# FMC_connector.net
KiCad netlist of a schematic drawn in Altium Designer
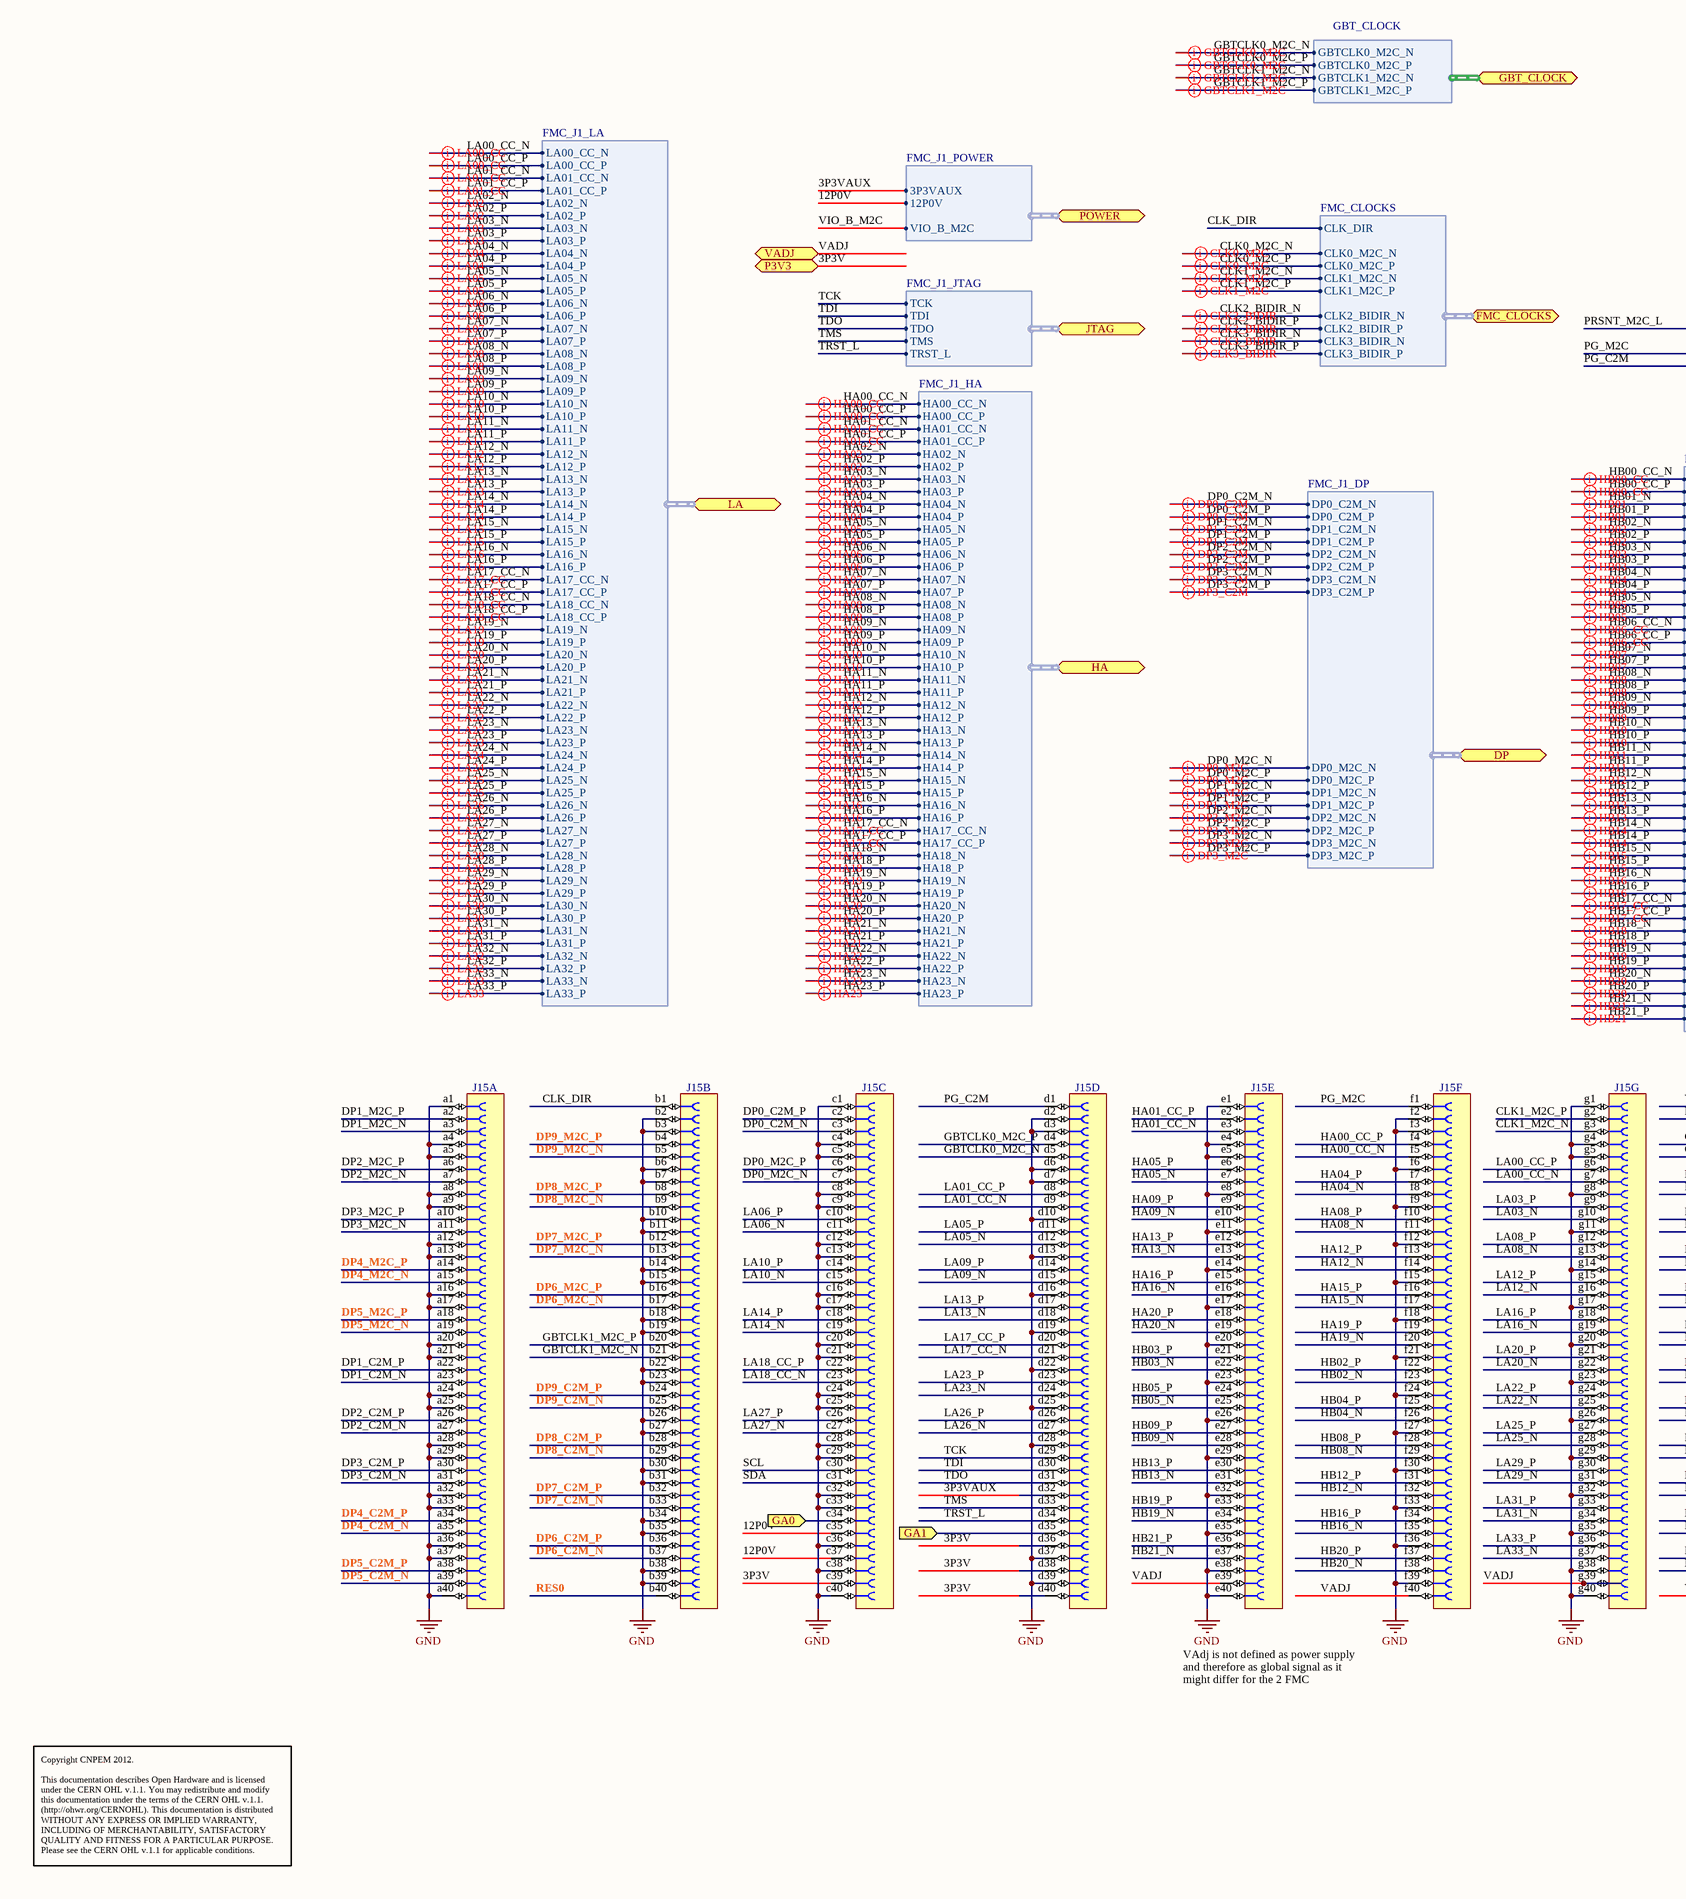
[diagram p0: FMC_connector.SchDoc, left]
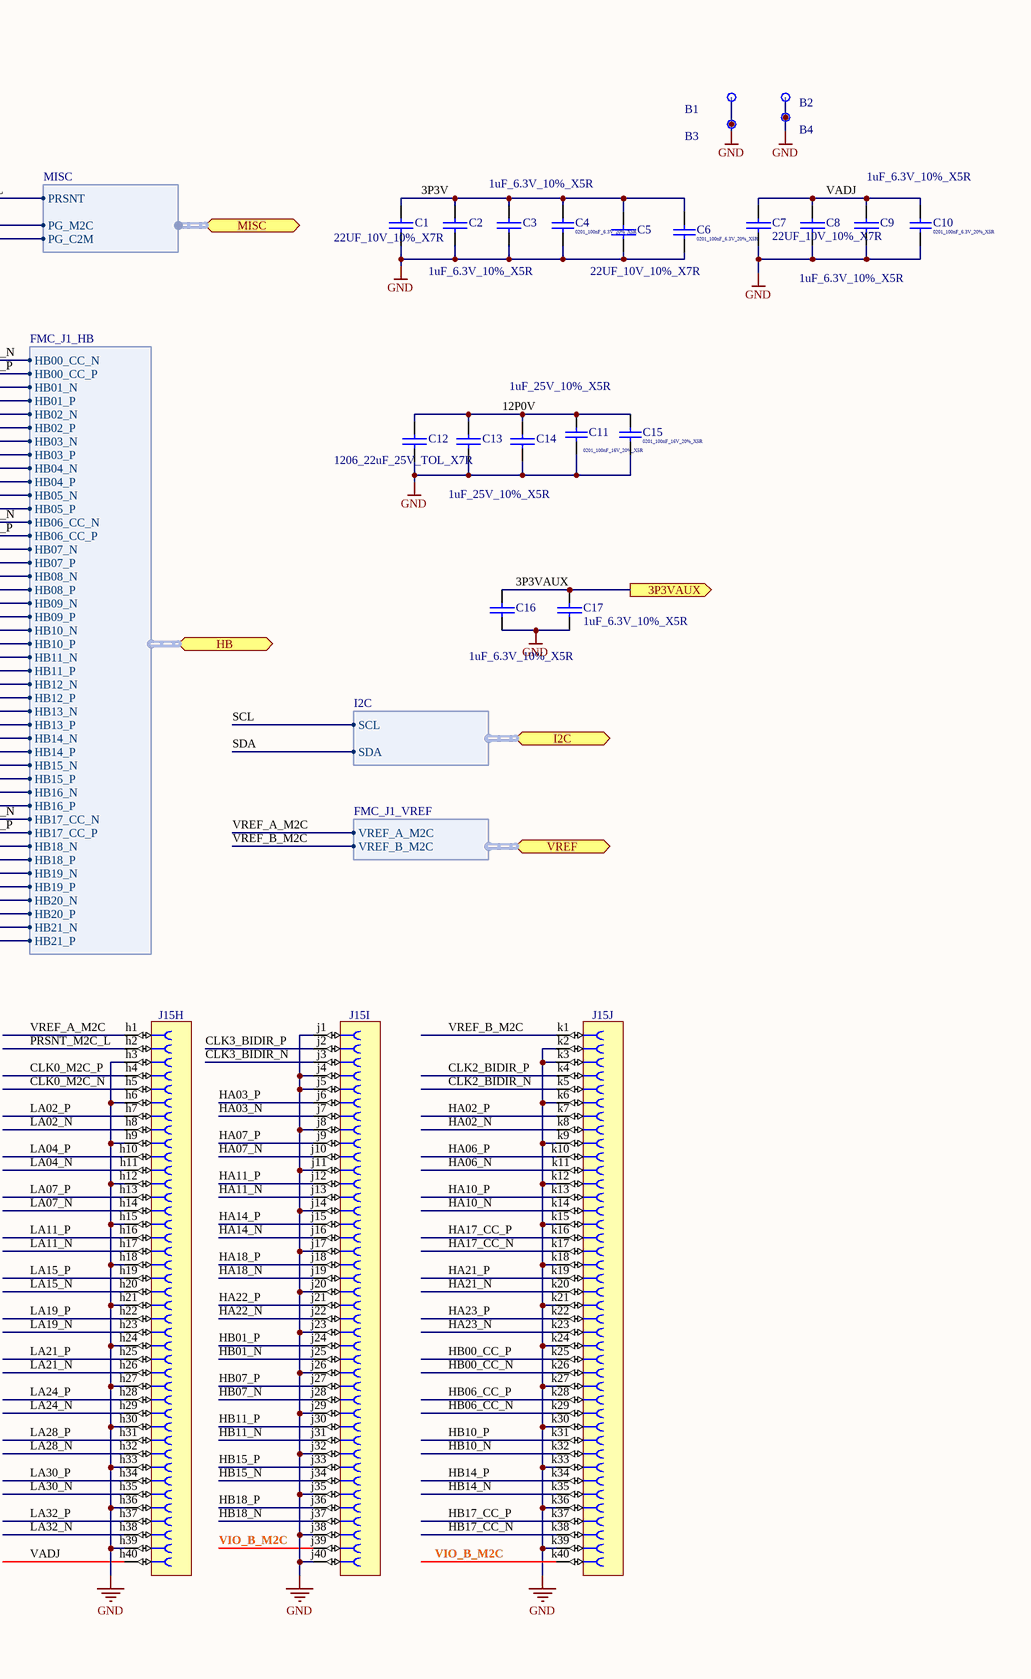
[diagram p1: FMC_connector.SchDoc, right]

(export (version "E")
  (design (tool "Eeschema 10.0.6"))
  (components
    (comp (ref "B1")
      (value "Plated Hole")
      (footprint "MTG270_500")
      (description "Single Terminal Socket")
      (fields (field (name "PART NUMBER") "PLATED_HOLE2.7_PAD5.0") (field (name "AUTHOR") "CERN DEM JMW"))
      (libsource (lib "Eletro-mechanical") (part "Single Terminal Socket"))
    )
    (comp (ref "B2")
      (value "Plated Hole")
      (footprint "MTG270_500")
      (description "Single Terminal Socket")
      (fields (field (name "PART NUMBER") "PLATED_HOLE2.7_PAD5.0") (field (name "AUTHOR") "CERN DEM JMW"))
      (libsource (lib "Eletro-mechanical") (part "Single Terminal Socket"))
    )
    (comp (ref "B3")
      (value "Plated Hole")
      (footprint "MTG270_500")
      (description "Single Terminal Socket")
      (fields (field (name "PART NUMBER") "PLATED_HOLE2.7_PAD5.0") (field (name "AUTHOR") "CERN DEM JMW"))
      (libsource (lib "Eletro-mechanical") (part "Single Terminal Socket"))
    )
    (comp (ref "B4")
      (value "Plated Hole")
      (footprint "MTG270_500")
      (description "Single Terminal Socket")
      (fields (field (name "PART NUMBER") "PLATED_HOLE2.7_PAD5.0") (field (name "AUTHOR") "CERN DEM JMW"))
      (libsource (lib "Eletro-mechanical") (part "Single Terminal Socket"))
    )
    (comp (ref "C1")
      (value "22UF_10V_10%_X7R")
      (footprint "1206C")
      (description "Capacitor SMD")
      (libsource (lib "LIBRARY_SCH") (part "CAP_SMD_1206"))
    )
    (comp (ref "C2")
      (value "1uF_6.3V_10%_X5R")
      (footprint "0603C")
      (description "Capacitor SMD")
      (libsource (lib "LIBRARY_SCH") (part "CAP_SMD_0603"))
    )
    (comp (ref "C3")
      (value "1uF_6.3V_10%_X5R")
      (footprint "0603C")
      (description "Capacitor SMD")
      (libsource (lib "LIBRARY_SCH") (part "CAP_SMD_0603"))
    )
    (comp (ref "C4")
      (value "0201_100nF_6.3V_20%_X5R")
      (footprint "CAPC0603X33N")
      (fields (field (name "PART NUMBER") "Ceramic_0201"))
      (libsource (lib "Capacitors") (part "Capacitor"))
    )
    (comp (ref "C5")
      (value "22UF_10V_10%_X7R")
      (footprint "1206C")
      (description "Capacitor SMD")
      (libsource (lib "LIBRARY_SCH") (part "CAP_SMD_1206"))
    )
    (comp (ref "C6")
      (value "0201_100nF_6.3V_20%_X5R")
      (footprint "CAPC0603X33N")
      (fields (field (name "PART NUMBER") "Ceramic_0201"))
      (libsource (lib "Capacitors") (part "Capacitor"))
    )
    (comp (ref "C7")
      (value "22UF_10V_10%_X7R")
      (footprint "1206C")
      (description "Capacitor SMD")
      (libsource (lib "LIBRARY_SCH") (part "CAP_SMD_1206"))
    )
    (comp (ref "C8")
      (value "1uF_6.3V_10%_X5R")
      (footprint "0603C")
      (description "Capacitor SMD")
      (libsource (lib "LIBRARY_SCH") (part "CAP_SMD_0603"))
    )
    (comp (ref "C9")
      (value "1uF_6.3V_10%_X5R")
      (footprint "0603C")
      (description "Capacitor SMD")
      (libsource (lib "LIBRARY_SCH") (part "CAP_SMD_0603"))
    )
    (comp (ref "C10")
      (value "0201_100nF_6.3V_20%_X5R")
      (footprint "CAPC0603X33N")
      (fields (field (name "PART NUMBER") "Ceramic_0201"))
      (libsource (lib "Capacitors") (part "Capacitor"))
    )
    (comp (ref "C11")
      (value "0201_100nF_16V_20%_X5R")
      (footprint "CAPC0603X33N")
      (fields (field (name "PART NUMBER") "Ceramic_0201"))
      (libsource (lib "Capacitors") (part "Capacitor"))
    )
    (comp (ref "C12")
      (value "1206_22uF_25V_TOL_X7R")
      (footprint "1206C")
      (description "Capacitor SMD")
      (libsource (lib "LIBRARY_SCH") (part "CAP_SMD_1206"))
    )
    (comp (ref "C13")
      (value "1uF_25V_10%_X5R")
      (footprint "0603C")
      (description "Capacitor SMD")
      (libsource (lib "LIBRARY_SCH") (part "CAP_SMD_0603"))
    )
    (comp (ref "C14")
      (value "1uF_25V_10%_X5R")
      (footprint "0603C")
      (description "Capacitor SMD")
      (libsource (lib "LIBRARY_SCH") (part "CAP_SMD_0603"))
    )
    (comp (ref "C15")
      (value "0201_100nF_16V_20%_X5R")
      (footprint "CAPC0603X33N")
      (fields (field (name "PART NUMBER") "Ceramic_0201"))
      (libsource (lib "Capacitors") (part "Capacitor"))
    )
    (comp (ref "C16")
      (value "1uF_6.3V_10%_X5R")
      (footprint "0603C")
      (description "Capacitor SMD")
      (libsource (lib "LIBRARY_SCH") (part "CAP_SMD_0603"))
    )
    (comp (ref "C17")
      (value "1uF_6.3V_10%_X5R")
      (footprint "0603C")
      (description "Capacitor SMD")
      (libsource (lib "LIBRARY_SCH") (part "CAP_SMD_0603"))
    )
    (comp (ref "J15")
      (value "VITA 57")
      (footprint "SAMTEC_ASP-134486-01")
      (description "Connector VITA 57, 400 Female contacts in 10 row abcdefghj")
      (fields
        (field (name "PART NUMBER") "SAMTEC_ASP-134486-01")
        (field (name "MANUFACTURER") "SAMTEC")
        (field (name "AUTHOR") "CERN DEM JLC")
      )
      (libsource (lib "Connectors") (part "Connector VITA 57 400 Female (abcdefghjk)"))
    )
  )
  (nets
    (net (code "12") (name "/3P3V") (class "Default")
      (node (ref "C1") (pin "1") (pinfunction "1_1") (pintype "passive"))
      (node (ref "C2") (pin "1") (pinfunction "1_1") (pintype "passive"))
      (node (ref "C3") (pin "1") (pinfunction "1_1") (pintype "passive"))
      (node (ref "C4") (pin "2") (pinfunction "2_2") (pintype "passive"))
      (node (ref "C5") (pin "1") (pinfunction "1_1") (pintype "passive"))
      (node (ref "C6") (pin "2") (pinfunction "2_2") (pintype "passive"))
      (node (ref "J15") (pin "c39") (pinfunction "c39_c39") (pintype "bidirectional"))
      (node (ref "J15") (pin "d36") (pinfunction "d36_d36") (pintype "bidirectional"))
      (node (ref "J15") (pin "d38") (pinfunction "d38_d38") (pintype "bidirectional"))
      (node (ref "J15") (pin "d40") (pinfunction "d40_d40") (pintype "bidirectional"))
    )
    (net (code "13") (name "/3P3VAUX") (class "Default")
      (node (ref "C16") (pin "1") (pinfunction "1_1") (pintype "passive"))
      (node (ref "C17") (pin "1") (pinfunction "1_1") (pintype "passive"))
      (node (ref "J15") (pin "d32") (pinfunction "d32_d32") (pintype "bidirectional"))
    )
    (net (code "14") (name "/12P0V") (class "Default")
      (node (ref "C11") (pin "2") (pinfunction "2_2") (pintype "passive"))
      (node (ref "C12") (pin "1") (pinfunction "1_1") (pintype "passive"))
      (node (ref "C13") (pin "1") (pinfunction "1_1") (pintype "passive"))
      (node (ref "C14") (pin "1") (pinfunction "1_1") (pintype "passive"))
      (node (ref "C15") (pin "2") (pinfunction "2_2") (pintype "passive"))
      (node (ref "J15") (pin "c35") (pinfunction "c35_c35") (pintype "bidirectional"))
      (node (ref "J15") (pin "c37") (pinfunction "c37_c37") (pintype "bidirectional"))
    )
    (net (code "15") (name "/CLK0_M2C_N") (class "Default")
      (node (ref "J15") (pin "h5") (pinfunction "h5_h5") (pintype "bidirectional"))
    )
    (net (code "16") (name "/CLK0_M2C_P") (class "Default")
      (node (ref "J15") (pin "h4") (pinfunction "h4_h4") (pintype "bidirectional"))
    )
    (net (code "17") (name "/CLK1_M2C_N") (class "Default")
      (node (ref "J15") (pin "g3") (pinfunction "g3_g3") (pintype "bidirectional"))
    )
    (net (code "18") (name "/CLK1_M2C_P") (class "Default")
      (node (ref "J15") (pin "g2") (pinfunction "g2_g2") (pintype "bidirectional"))
    )
    (net (code "19") (name "/CLK2_BIDIR_N") (class "Default")
      (node (ref "J15") (pin "k5") (pinfunction "k5_k5") (pintype "bidirectional"))
    )
    (net (code "20") (name "/CLK2_BIDIR_P") (class "Default")
      (node (ref "J15") (pin "k4") (pinfunction "k4_k4") (pintype "bidirectional"))
    )
    (net (code "21") (name "/CLK3_BIDIR_N") (class "Default")
      (node (ref "J15") (pin "j3") (pinfunction "j3_j3") (pintype "bidirectional"))
    )
    (net (code "22") (name "/CLK3_BIDIR_P") (class "Default")
      (node (ref "J15") (pin "j2") (pinfunction "j2_j2") (pintype "bidirectional"))
    )
    (net (code "23") (name "/CLK_DIR") (class "Default")
      (node (ref "J15") (pin "b1") (pinfunction "b1_b1") (pintype "bidirectional"))
    )
    (net (code "24") (name "/DP0_C2M_N") (class "Default")
      (node (ref "J15") (pin "c3") (pinfunction "c3_c3") (pintype "bidirectional"))
    )
    (net (code "25") (name "/DP0_C2M_P") (class "Default")
      (node (ref "J15") (pin "c2") (pinfunction "c2_c2") (pintype "bidirectional"))
    )
    (net (code "26") (name "/DP0_M2C_N") (class "Default")
      (node (ref "J15") (pin "c7") (pinfunction "c7_c7") (pintype "bidirectional"))
    )
    (net (code "27") (name "/DP0_M2C_P") (class "Default")
      (node (ref "J15") (pin "c6") (pinfunction "c6_c6") (pintype "bidirectional"))
    )
    (net (code "28") (name "/DP1_C2M_N") (class "Default")
      (node (ref "J15") (pin "a23") (pinfunction "a23_a23") (pintype "bidirectional"))
    )
    (net (code "29") (name "/DP1_C2M_P") (class "Default")
      (node (ref "J15") (pin "a22") (pinfunction "a22_a22") (pintype "bidirectional"))
    )
    (net (code "30") (name "/DP1_M2C_N") (class "Default")
      (node (ref "J15") (pin "a3") (pinfunction "a3_a3") (pintype "bidirectional"))
    )
    (net (code "31") (name "/DP1_M2C_P") (class "Default")
      (node (ref "J15") (pin "a2") (pinfunction "a2_a2") (pintype "bidirectional"))
    )
    (net (code "32") (name "/DP2_C2M_N") (class "Default")
      (node (ref "J15") (pin "a27") (pinfunction "a27_a27") (pintype "bidirectional"))
    )
    (net (code "33") (name "/DP2_C2M_P") (class "Default")
      (node (ref "J15") (pin "a26") (pinfunction "a26_a26") (pintype "bidirectional"))
    )
    (net (code "34") (name "/DP2_M2C_N") (class "Default")
      (node (ref "J15") (pin "a7") (pinfunction "a7_a7") (pintype "bidirectional"))
    )
    (net (code "35") (name "/DP2_M2C_P") (class "Default")
      (node (ref "J15") (pin "a6") (pinfunction "a6_a6") (pintype "bidirectional"))
    )
    (net (code "36") (name "/DP3_C2M_N") (class "Default")
      (node (ref "J15") (pin "a31") (pinfunction "a31_a31") (pintype "bidirectional"))
    )
    (net (code "37") (name "/DP3_C2M_P") (class "Default")
      (node (ref "J15") (pin "a30") (pinfunction "a30_a30") (pintype "bidirectional"))
    )
    (net (code "38") (name "/DP3_M2C_N") (class "Default")
      (node (ref "J15") (pin "a11") (pinfunction "a11_a11") (pintype "bidirectional"))
    )
    (net (code "39") (name "/DP3_M2C_P") (class "Default")
      (node (ref "J15") (pin "a10") (pinfunction "a10_a10") (pintype "bidirectional"))
    )
    (net (code "40") (name "/GA0") (class "Default")
      (node (ref "J15") (pin "c34") (pinfunction "c34_c34") (pintype "bidirectional"))
    )
    (net (code "41") (name "/GA1") (class "Default")
      (node (ref "J15") (pin "d35") (pinfunction "d35_d35") (pintype "bidirectional"))
    )
    (net (code "42") (name "/GBTCLK0_M2C_N") (class "Default")
      (node (ref "J15") (pin "d5") (pinfunction "d5_d5") (pintype "bidirectional"))
    )
    (net (code "43") (name "/GBTCLK0_M2C_P") (class "Default")
      (node (ref "J15") (pin "d4") (pinfunction "d4_d4") (pintype "bidirectional"))
    )
    (net (code "44") (name "/GBTCLK1_M2C_N") (class "Default")
      (node (ref "J15") (pin "b21") (pinfunction "b21_b21") (pintype "bidirectional"))
    )
    (net (code "45") (name "/GBTCLK1_M2C_P") (class "Default")
      (node (ref "J15") (pin "b20") (pinfunction "b20_b20") (pintype "bidirectional"))
    )
    (net (code "46") (name "/HA00_CC_N") (class "Default")
      (node (ref "J15") (pin "f5") (pinfunction "f5_f5") (pintype "bidirectional"))
    )
    (net (code "47") (name "/HA00_CC_P") (class "Default")
      (node (ref "J15") (pin "f4") (pinfunction "f4_f4") (pintype "bidirectional"))
    )
    (net (code "48") (name "/HA01_CC_N") (class "Default")
      (node (ref "J15") (pin "e3") (pinfunction "e3_e3") (pintype "bidirectional"))
    )
    (net (code "49") (name "/HA01_CC_P") (class "Default")
      (node (ref "J15") (pin "e2") (pinfunction "e2_e2") (pintype "bidirectional"))
    )
    (net (code "50") (name "/HA02_N") (class "Default")
      (node (ref "J15") (pin "k8") (pinfunction "k8_k8") (pintype "bidirectional"))
    )
    (net (code "51") (name "/HA02_P") (class "Default")
      (node (ref "J15") (pin "k7") (pinfunction "k7_k7") (pintype "bidirectional"))
    )
    (net (code "52") (name "/HA03_N") (class "Default")
      (node (ref "J15") (pin "j7") (pinfunction "j7_j7") (pintype "bidirectional"))
    )
    (net (code "53") (name "/HA03_P") (class "Default")
      (node (ref "J15") (pin "j6") (pinfunction "j6_j6") (pintype "bidirectional"))
    )
    (net (code "54") (name "/HA04_N") (class "Default")
      (node (ref "J15") (pin "f8") (pinfunction "f8_f8") (pintype "bidirectional"))
    )
    (net (code "55") (name "/HA04_P") (class "Default")
      (node (ref "J15") (pin "f7") (pinfunction "f7_f7") (pintype "bidirectional"))
    )
    (net (code "56") (name "/HA05_N") (class "Default")
      (node (ref "J15") (pin "e7") (pinfunction "e7_e7") (pintype "bidirectional"))
    )
    (net (code "57") (name "/HA05_P") (class "Default")
      (node (ref "J15") (pin "e6") (pinfunction "e6_e6") (pintype "bidirectional"))
    )
    (net (code "58") (name "/HA06_N") (class "Default")
      (node (ref "J15") (pin "k11") (pinfunction "k11_k11") (pintype "bidirectional"))
    )
    (net (code "59") (name "/HA06_P") (class "Default")
      (node (ref "J15") (pin "k10") (pinfunction "k10_k10") (pintype "bidirectional"))
    )
    (net (code "60") (name "/HA07_N") (class "Default")
      (node (ref "J15") (pin "j10") (pinfunction "j10_j10") (pintype "bidirectional"))
    )
    (net (code "61") (name "/HA07_P") (class "Default")
      (node (ref "J15") (pin "j9") (pinfunction "j9_j9") (pintype "bidirectional"))
    )
    (net (code "62") (name "/HA08_N") (class "Default")
      (node (ref "J15") (pin "f11") (pinfunction "f11_f11") (pintype "bidirectional"))
    )
    (net (code "63") (name "/HA08_P") (class "Default")
      (node (ref "J15") (pin "f10") (pinfunction "f10_f10") (pintype "bidirectional"))
    )
    (net (code "64") (name "/HA09_N") (class "Default")
      (node (ref "J15") (pin "e10") (pinfunction "e10_e10") (pintype "bidirectional"))
    )
    (net (code "65") (name "/HA09_P") (class "Default")
      (node (ref "J15") (pin "e9") (pinfunction "e9_e9") (pintype "bidirectional"))
    )
    (net (code "66") (name "/HA10_N") (class "Default")
      (node (ref "J15") (pin "k14") (pinfunction "k14_k14") (pintype "bidirectional"))
    )
    (net (code "67") (name "/HA10_P") (class "Default")
      (node (ref "J15") (pin "k13") (pinfunction "k13_k13") (pintype "bidirectional"))
    )
    (net (code "68") (name "/HA11_N") (class "Default")
      (node (ref "J15") (pin "j13") (pinfunction "j13_j13") (pintype "bidirectional"))
    )
    (net (code "69") (name "/HA11_P") (class "Default")
      (node (ref "J15") (pin "j12") (pinfunction "j12_j12") (pintype "bidirectional"))
    )
    (net (code "70") (name "/HA12_N") (class "Default")
      (node (ref "J15") (pin "f14") (pinfunction "f14_f14") (pintype "bidirectional"))
    )
    (net (code "71") (name "/HA12_P") (class "Default")
      (node (ref "J15") (pin "f13") (pinfunction "f13_f13") (pintype "bidirectional"))
    )
    (net (code "72") (name "/HA13_N") (class "Default")
      (node (ref "J15") (pin "e13") (pinfunction "e13_e13") (pintype "bidirectional"))
    )
    (net (code "73") (name "/HA13_P") (class "Default")
      (node (ref "J15") (pin "e12") (pinfunction "e12_e12") (pintype "bidirectional"))
    )
    (net (code "74") (name "/HA14_N") (class "Default")
      (node (ref "J15") (pin "j16") (pinfunction "j16_j16") (pintype "bidirectional"))
    )
    (net (code "75") (name "/HA14_P") (class "Default")
      (node (ref "J15") (pin "j15") (pinfunction "j15_j15") (pintype "bidirectional"))
    )
    (net (code "76") (name "/HA15_N") (class "Default")
      (node (ref "J15") (pin "f17") (pinfunction "f17_f17") (pintype "bidirectional"))
    )
    (net (code "77") (name "/HA15_P") (class "Default")
      (node (ref "J15") (pin "f16") (pinfunction "f16_f16") (pintype "bidirectional"))
    )
    (net (code "78") (name "/HA16_N") (class "Default")
      (node (ref "J15") (pin "e16") (pinfunction "e16_e16") (pintype "bidirectional"))
    )
    (net (code "79") (name "/HA16_P") (class "Default")
      (node (ref "J15") (pin "e15") (pinfunction "e15_e15") (pintype "bidirectional"))
    )
    (net (code "80") (name "/HA17_CC_N") (class "Default")
      (node (ref "J15") (pin "k17") (pinfunction "k17_k17") (pintype "bidirectional"))
    )
    (net (code "81") (name "/HA17_CC_P") (class "Default")
      (node (ref "J15") (pin "k16") (pinfunction "k16_k16") (pintype "bidirectional"))
    )
    (net (code "82") (name "/HA18_N") (class "Default")
      (node (ref "J15") (pin "j19") (pinfunction "j19_j19") (pintype "bidirectional"))
    )
    (net (code "83") (name "/HA18_P") (class "Default")
      (node (ref "J15") (pin "j18") (pinfunction "j18_j18") (pintype "bidirectional"))
    )
    (net (code "84") (name "/HA19_N") (class "Default")
      (node (ref "J15") (pin "f20") (pinfunction "f20_f20") (pintype "bidirectional"))
    )
    (net (code "85") (name "/HA19_P") (class "Default")
      (node (ref "J15") (pin "f19") (pinfunction "f19_f19") (pintype "bidirectional"))
    )
    (net (code "86") (name "/HA20_N") (class "Default")
      (node (ref "J15") (pin "e19") (pinfunction "e19_e19") (pintype "bidirectional"))
    )
    (net (code "87") (name "/HA20_P") (class "Default")
      (node (ref "J15") (pin "e18") (pinfunction "e18_e18") (pintype "bidirectional"))
    )
    (net (code "88") (name "/HA21_N") (class "Default")
      (node (ref "J15") (pin "k20") (pinfunction "k20_k20") (pintype "bidirectional"))
    )
    (net (code "89") (name "/HA21_P") (class "Default")
      (node (ref "J15") (pin "k19") (pinfunction "k19_k19") (pintype "bidirectional"))
    )
    (net (code "90") (name "/HA22_N") (class "Default")
      (node (ref "J15") (pin "j22") (pinfunction "j22_j22") (pintype "bidirectional"))
    )
    (net (code "91") (name "/HA22_P") (class "Default")
      (node (ref "J15") (pin "j21") (pinfunction "j21_j21") (pintype "bidirectional"))
    )
    (net (code "92") (name "/HA23_N") (class "Default")
      (node (ref "J15") (pin "k23") (pinfunction "k23_k23") (pintype "bidirectional"))
    )
    (net (code "93") (name "/HA23_P") (class "Default")
      (node (ref "J15") (pin "k22") (pinfunction "k22_k22") (pintype "bidirectional"))
    )
    (net (code "94") (name "/HB00_CC_N") (class "Default")
      (node (ref "J15") (pin "k26") (pinfunction "k26_k26") (pintype "bidirectional"))
    )
    (net (code "95") (name "/HB00_CC_P") (class "Default")
      (node (ref "J15") (pin "k25") (pinfunction "k25_k25") (pintype "bidirectional"))
    )
    (net (code "96") (name "/HB01_N") (class "Default")
      (node (ref "J15") (pin "j25") (pinfunction "j25_j25") (pintype "bidirectional"))
    )
    (net (code "97") (name "/HB01_P") (class "Default")
      (node (ref "J15") (pin "j24") (pinfunction "j24_j24") (pintype "bidirectional"))
    )
    (net (code "98") (name "/HB02_N") (class "Default")
      (node (ref "J15") (pin "f23") (pinfunction "f23_f23") (pintype "bidirectional"))
    )
    (net (code "99") (name "/HB02_P") (class "Default")
      (node (ref "J15") (pin "f22") (pinfunction "f22_f22") (pintype "bidirectional"))
    )
    (net (code "100") (name "/HB03_N") (class "Default")
      (node (ref "J15") (pin "e22") (pinfunction "e22_e22") (pintype "bidirectional"))
    )
    (net (code "101") (name "/HB03_P") (class "Default")
      (node (ref "J15") (pin "e21") (pinfunction "e21_e21") (pintype "bidirectional"))
    )
    (net (code "102") (name "/HB04_N") (class "Default")
      (node (ref "J15") (pin "f26") (pinfunction "f26_f26") (pintype "bidirectional"))
    )
    (net (code "103") (name "/HB04_P") (class "Default")
      (node (ref "J15") (pin "f25") (pinfunction "f25_f25") (pintype "bidirectional"))
    )
    (net (code "104") (name "/HB05_N") (class "Default")
      (node (ref "J15") (pin "e25") (pinfunction "e25_e25") (pintype "bidirectional"))
    )
    (net (code "105") (name "/HB05_P") (class "Default")
      (node (ref "J15") (pin "e24") (pinfunction "e24_e24") (pintype "bidirectional"))
    )
    (net (code "106") (name "/HB06_CC_N") (class "Default")
      (node (ref "J15") (pin "k29") (pinfunction "k29_k29") (pintype "bidirectional"))
    )
    (net (code "107") (name "/HB06_CC_P") (class "Default")
      (node (ref "J15") (pin "k28") (pinfunction "k28_k28") (pintype "bidirectional"))
    )
    (net (code "108") (name "/HB07_N") (class "Default")
      (node (ref "J15") (pin "j28") (pinfunction "j28_j28") (pintype "bidirectional"))
    )
    (net (code "109") (name "/HB07_P") (class "Default")
      (node (ref "J15") (pin "j27") (pinfunction "j27_j27") (pintype "bidirectional"))
    )
    (net (code "110") (name "/HB08_N") (class "Default")
      (node (ref "J15") (pin "f29") (pinfunction "f29_f29") (pintype "bidirectional"))
    )
    (net (code "111") (name "/HB08_P") (class "Default")
      (node (ref "J15") (pin "f28") (pinfunction "f28_f28") (pintype "bidirectional"))
    )
    (net (code "112") (name "/HB09_N") (class "Default")
      (node (ref "J15") (pin "e28") (pinfunction "e28_e28") (pintype "bidirectional"))
    )
    (net (code "113") (name "/HB09_P") (class "Default")
      (node (ref "J15") (pin "e27") (pinfunction "e27_e27") (pintype "bidirectional"))
    )
    (net (code "114") (name "/HB10_N") (class "Default")
      (node (ref "J15") (pin "k32") (pinfunction "k32_k32") (pintype "bidirectional"))
    )
    (net (code "115") (name "/HB10_P") (class "Default")
      (node (ref "J15") (pin "k31") (pinfunction "k31_k31") (pintype "bidirectional"))
    )
    (net (code "116") (name "/HB11_N") (class "Default")
      (node (ref "J15") (pin "j31") (pinfunction "j31_j31") (pintype "bidirectional"))
    )
    (net (code "117") (name "/HB11_P") (class "Default")
      (node (ref "J15") (pin "j30") (pinfunction "j30_j30") (pintype "bidirectional"))
    )
    (net (code "118") (name "/HB12_N") (class "Default")
      (node (ref "J15") (pin "f32") (pinfunction "f32_f32") (pintype "bidirectional"))
    )
    (net (code "119") (name "/HB12_P") (class "Default")
      (node (ref "J15") (pin "f31") (pinfunction "f31_f31") (pintype "bidirectional"))
    )
    (net (code "120") (name "/HB13_N") (class "Default")
      (node (ref "J15") (pin "e31") (pinfunction "e31_e31") (pintype "bidirectional"))
    )
    (net (code "121") (name "/HB13_P") (class "Default")
      (node (ref "J15") (pin "e30") (pinfunction "e30_e30") (pintype "bidirectional"))
    )
    (net (code "122") (name "/HB14_N") (class "Default")
      (node (ref "J15") (pin "k35") (pinfunction "k35_k35") (pintype "bidirectional"))
    )
    (net (code "123") (name "/HB14_P") (class "Default")
      (node (ref "J15") (pin "k34") (pinfunction "k34_k34") (pintype "bidirectional"))
    )
    (net (code "124") (name "/HB15_N") (class "Default")
      (node (ref "J15") (pin "j34") (pinfunction "j34_j34") (pintype "bidirectional"))
    )
    (net (code "125") (name "/HB15_P") (class "Default")
      (node (ref "J15") (pin "j33") (pinfunction "j33_j33") (pintype "bidirectional"))
    )
    (net (code "126") (name "/HB16_N") (class "Default")
      (node (ref "J15") (pin "f35") (pinfunction "f35_f35") (pintype "bidirectional"))
    )
    (net (code "127") (name "/HB16_P") (class "Default")
      (node (ref "J15") (pin "f34") (pinfunction "f34_f34") (pintype "bidirectional"))
    )
    (net (code "128") (name "/HB17_CC_N") (class "Default")
      (node (ref "J15") (pin "k38") (pinfunction "k38_k38") (pintype "bidirectional"))
    )
    (net (code "129") (name "/HB17_CC_P") (class "Default")
      (node (ref "J15") (pin "k37") (pinfunction "k37_k37") (pintype "bidirectional"))
    )
    (net (code "130") (name "/HB18_N") (class "Default")
      (node (ref "J15") (pin "j37") (pinfunction "j37_j37") (pintype "bidirectional"))
    )
    (net (code "131") (name "/HB18_P") (class "Default")
      (node (ref "J15") (pin "j36") (pinfunction "j36_j36") (pintype "bidirectional"))
    )
    (net (code "132") (name "/HB19_N") (class "Default")
      (node (ref "J15") (pin "e34") (pinfunction "e34_e34") (pintype "bidirectional"))
    )
    (net (code "133") (name "/HB19_P") (class "Default")
      (node (ref "J15") (pin "e33") (pinfunction "e33_e33") (pintype "bidirectional"))
    )
    (net (code "134") (name "/HB20_N") (class "Default")
      (node (ref "J15") (pin "f38") (pinfunction "f38_f38") (pintype "bidirectional"))
    )
    (net (code "135") (name "/HB20_P") (class "Default")
      (node (ref "J15") (pin "f37") (pinfunction "f37_f37") (pintype "bidirectional"))
    )
    (net (code "136") (name "/HB21_N") (class "Default")
      (node (ref "J15") (pin "e37") (pinfunction "e37_e37") (pintype "bidirectional"))
    )
    (net (code "137") (name "/HB21_P") (class "Default")
      (node (ref "J15") (pin "e36") (pinfunction "e36_e36") (pintype "bidirectional"))
    )
    (net (code "138") (name "/LA00_CC_N") (class "Default")
      (node (ref "J15") (pin "g7") (pinfunction "g7_g7") (pintype "bidirectional"))
    )
    (net (code "139") (name "/LA00_CC_P") (class "Default")
      (node (ref "J15") (pin "g6") (pinfunction "g6_g6") (pintype "bidirectional"))
    )
    (net (code "140") (name "/LA01_CC_N") (class "Default")
      (node (ref "J15") (pin "d9") (pinfunction "d9_d9") (pintype "bidirectional"))
    )
    (net (code "141") (name "/LA01_CC_P") (class "Default")
      (node (ref "J15") (pin "d8") (pinfunction "d8_d8") (pintype "bidirectional"))
    )
    (net (code "142") (name "/LA02_N") (class "Default")
      (node (ref "J15") (pin "h8") (pinfunction "h8_h8") (pintype "bidirectional"))
    )
    (net (code "143") (name "/LA02_P") (class "Default")
      (node (ref "J15") (pin "h7") (pinfunction "h7_h7") (pintype "bidirectional"))
    )
    (net (code "144") (name "/LA03_N") (class "Default")
      (node (ref "J15") (pin "g10") (pinfunction "g10_g10") (pintype "bidirectional"))
    )
    (net (code "145") (name "/LA03_P") (class "Default")
      (node (ref "J15") (pin "g9") (pinfunction "g9_g9") (pintype "bidirectional"))
    )
    (net (code "146") (name "/LA04_N") (class "Default")
      (node (ref "J15") (pin "h11") (pinfunction "h11_h11") (pintype "bidirectional"))
    )
    (net (code "147") (name "/LA04_P") (class "Default")
      (node (ref "J15") (pin "h10") (pinfunction "h10_h10") (pintype "bidirectional"))
    )
    (net (code "148") (name "/LA05_N") (class "Default")
      (node (ref "J15") (pin "d12") (pinfunction "d12_d12") (pintype "bidirectional"))
    )
    (net (code "149") (name "/LA05_P") (class "Default")
      (node (ref "J15") (pin "d11") (pinfunction "d11_d11") (pintype "bidirectional"))
    )
    (net (code "150") (name "/LA06_N") (class "Default")
      (node (ref "J15") (pin "c11") (pinfunction "c11_c11") (pintype "bidirectional"))
    )
    (net (code "151") (name "/LA06_P") (class "Default")
      (node (ref "J15") (pin "c10") (pinfunction "c10_c10") (pintype "bidirectional"))
    )
    (net (code "152") (name "/LA07_N") (class "Default")
      (node (ref "J15") (pin "h14") (pinfunction "h14_h14") (pintype "bidirectional"))
    )
    (net (code "153") (name "/LA07_P") (class "Default")
      (node (ref "J15") (pin "h13") (pinfunction "h13_h13") (pintype "bidirectional"))
    )
    (net (code "154") (name "/LA08_N") (class "Default")
      (node (ref "J15") (pin "g13") (pinfunction "g13_g13") (pintype "bidirectional"))
    )
    (net (code "155") (name "/LA08_P") (class "Default")
      (node (ref "J15") (pin "g12") (pinfunction "g12_g12") (pintype "bidirectional"))
    )
    (net (code "156") (name "/LA09_N") (class "Default")
      (node (ref "J15") (pin "d15") (pinfunction "d15_d15") (pintype "bidirectional"))
    )
    (net (code "157") (name "/LA09_P") (class "Default")
      (node (ref "J15") (pin "d14") (pinfunction "d14_d14") (pintype "bidirectional"))
    )
    (net (code "158") (name "/LA10_N") (class "Default")
      (node (ref "J15") (pin "c15") (pinfunction "c15_c15") (pintype "bidirectional"))
    )
    (net (code "159") (name "/LA10_P") (class "Default")
      (node (ref "J15") (pin "c14") (pinfunction "c14_c14") (pintype "bidirectional"))
    )
    (net (code "160") (name "/LA11_N") (class "Default")
      (node (ref "J15") (pin "h17") (pinfunction "h17_h17") (pintype "bidirectional"))
    )
    (net (code "161") (name "/LA11_P") (class "Default")
      (node (ref "J15") (pin "h16") (pinfunction "h16_h16") (pintype "bidirectional"))
    )
    (net (code "162") (name "/LA12_N") (class "Default")
      (node (ref "J15") (pin "g16") (pinfunction "g16_g16") (pintype "bidirectional"))
    )
    (net (code "163") (name "/LA12_P") (class "Default")
      (node (ref "J15") (pin "g15") (pinfunction "g15_g15") (pintype "bidirectional"))
    )
    (net (code "164") (name "/LA13_N") (class "Default")
      (node (ref "J15") (pin "d18") (pinfunction "d18_d18") (pintype "bidirectional"))
    )
    (net (code "165") (name "/LA13_P") (class "Default")
      (node (ref "J15") (pin "d17") (pinfunction "d17_d17") (pintype "bidirectional"))
    )
    (net (code "166") (name "/LA14_N") (class "Default")
      (node (ref "J15") (pin "c19") (pinfunction "c19_c19") (pintype "bidirectional"))
    )
    (net (code "167") (name "/LA14_P") (class "Default")
      (node (ref "J15") (pin "c18") (pinfunction "c18_c18") (pintype "bidirectional"))
    )
    (net (code "168") (name "/LA15_N") (class "Default")
      (node (ref "J15") (pin "h20") (pinfunction "h20_h20") (pintype "bidirectional"))
    )
    (net (code "169") (name "/LA15_P") (class "Default")
      (node (ref "J15") (pin "h19") (pinfunction "h19_h19") (pintype "bidirectional"))
    )
    (net (code "170") (name "/LA16_N") (class "Default")
      (node (ref "J15") (pin "g19") (pinfunction "g19_g19") (pintype "bidirectional"))
    )
    (net (code "171") (name "/LA16_P") (class "Default")
      (node (ref "J15") (pin "g18") (pinfunction "g18_g18") (pintype "bidirectional"))
    )
    (net (code "172") (name "/LA17_CC_N") (class "Default")
      (node (ref "J15") (pin "d21") (pinfunction "d21_d21") (pintype "bidirectional"))
    )
    (net (code "173") (name "/LA17_CC_P") (class "Default")
      (node (ref "J15") (pin "d20") (pinfunction "d20_d20") (pintype "bidirectional"))
    )
    (net (code "174") (name "/LA18_CC_N") (class "Default")
      (node (ref "J15") (pin "c23") (pinfunction "c23_c23") (pintype "bidirectional"))
    )
    (net (code "175") (name "/LA18_CC_P") (class "Default")
      (node (ref "J15") (pin "c22") (pinfunction "c22_c22") (pintype "bidirectional"))
    )
    (net (code "176") (name "/LA19_N") (class "Default")
      (node (ref "J15") (pin "h23") (pinfunction "h23_h23") (pintype "bidirectional"))
    )
    (net (code "177") (name "/LA19_P") (class "Default")
      (node (ref "J15") (pin "h22") (pinfunction "h22_h22") (pintype "bidirectional"))
    )
    (net (code "178") (name "/LA20_N") (class "Default")
      (node (ref "J15") (pin "g22") (pinfunction "g22_g22") (pintype "bidirectional"))
    )
    (net (code "179") (name "/LA20_P") (class "Default")
      (node (ref "J15") (pin "g21") (pinfunction "g21_g21") (pintype "bidirectional"))
    )
    (net (code "180") (name "/LA21_N") (class "Default")
      (node (ref "J15") (pin "h26") (pinfunction "h26_h26") (pintype "bidirectional"))
    )
    (net (code "181") (name "/LA21_P") (class "Default")
      (node (ref "J15") (pin "h25") (pinfunction "h25_h25") (pintype "bidirectional"))
    )
    (net (code "182") (name "/LA22_N") (class "Default")
      (node (ref "J15") (pin "g25") (pinfunction "g25_g25") (pintype "bidirectional"))
    )
    (net (code "183") (name "/LA22_P") (class "Default")
      (node (ref "J15") (pin "g24") (pinfunction "g24_g24") (pintype "bidirectional"))
    )
    (net (code "184") (name "/LA23_N") (class "Default")
      (node (ref "J15") (pin "d24") (pinfunction "d24_d24") (pintype "bidirectional"))
    )
    (net (code "185") (name "/LA23_P") (class "Default")
      (node (ref "J15") (pin "d23") (pinfunction "d23_d23") (pintype "bidirectional"))
    )
    (net (code "186") (name "/LA24_N") (class "Default")
      (node (ref "J15") (pin "h29") (pinfunction "h29_h29") (pintype "bidirectional"))
    )
    (net (code "187") (name "/LA24_P") (class "Default")
      (node (ref "J15") (pin "h28") (pinfunction "h28_h28") (pintype "bidirectional"))
    )
    (net (code "188") (name "/LA25_N") (class "Default")
      (node (ref "J15") (pin "g28") (pinfunction "g28_g28") (pintype "bidirectional"))
    )
    (net (code "189") (name "/LA25_P") (class "Default")
      (node (ref "J15") (pin "g27") (pinfunction "g27_g27") (pintype "bidirectional"))
    )
    (net (code "190") (name "/LA26_N") (class "Default")
      (node (ref "J15") (pin "d27") (pinfunction "d27_d27") (pintype "bidirectional"))
    )
    (net (code "191") (name "/LA26_P") (class "Default")
      (node (ref "J15") (pin "d26") (pinfunction "d26_d26") (pintype "bidirectional"))
    )
    (net (code "192") (name "/LA27_N") (class "Default")
      (node (ref "J15") (pin "c27") (pinfunction "c27_c27") (pintype "bidirectional"))
    )
    (net (code "193") (name "/LA27_P") (class "Default")
      (node (ref "J15") (pin "c26") (pinfunction "c26_c26") (pintype "bidirectional"))
    )
    (net (code "194") (name "/LA28_N") (class "Default")
      (node (ref "J15") (pin "h32") (pinfunction "h32_h32") (pintype "bidirectional"))
    )
    (net (code "195") (name "/LA28_P") (class "Default")
      (node (ref "J15") (pin "h31") (pinfunction "h31_h31") (pintype "bidirectional"))
    )
    (net (code "196") (name "/LA29_N") (class "Default")
      (node (ref "J15") (pin "g31") (pinfunction "g31_g31") (pintype "bidirectional"))
    )
    (net (code "197") (name "/LA29_P") (class "Default")
      (node (ref "J15") (pin "g30") (pinfunction "g30_g30") (pintype "bidirectional"))
    )
    (net (code "198") (name "/LA30_N") (class "Default")
      (node (ref "J15") (pin "h35") (pinfunction "h35_h35") (pintype "bidirectional"))
    )
    (net (code "199") (name "/LA30_P") (class "Default")
      (node (ref "J15") (pin "h34") (pinfunction "h34_h34") (pintype "bidirectional"))
    )
    (net (code "200") (name "/LA31_N") (class "Default")
      (node (ref "J15") (pin "g34") (pinfunction "g34_g34") (pintype "bidirectional"))
    )
    (net (code "201") (name "/LA31_P") (class "Default")
      (node (ref "J15") (pin "g33") (pinfunction "g33_g33") (pintype "bidirectional"))
    )
    (net (code "202") (name "/LA32_N") (class "Default")
      (node (ref "J15") (pin "h38") (pinfunction "h38_h38") (pintype "bidirectional"))
    )
    (net (code "203") (name "/LA32_P") (class "Default")
      (node (ref "J15") (pin "h37") (pinfunction "h37_h37") (pintype "bidirectional"))
    )
    (net (code "204") (name "/LA33_N") (class "Default")
      (node (ref "J15") (pin "g37") (pinfunction "g37_g37") (pintype "bidirectional"))
    )
    (net (code "205") (name "/LA33_P") (class "Default")
      (node (ref "J15") (pin "g36") (pinfunction "g36_g36") (pintype "bidirectional"))
    )
    (net (code "206") (name "/PG_C2M") (class "Default")
      (node (ref "J15") (pin "d1") (pinfunction "d1_d1") (pintype "bidirectional"))
    )
    (net (code "207") (name "/PG_M2C") (class "Default")
      (node (ref "J15") (pin "f1") (pinfunction "f1_f1") (pintype "bidirectional"))
    )
    (net (code "208") (name "/PRSNT_M2C_L") (class "Default")
      (node (ref "J15") (pin "h2") (pinfunction "h2_h2") (pintype "bidirectional"))
    )
    (net (code "209") (name "/SCL") (class "Default")
      (node (ref "J15") (pin "c30") (pinfunction "c30_c30") (pintype "bidirectional"))
    )
    (net (code "210") (name "/SDA") (class "Default")
      (node (ref "J15") (pin "c31") (pinfunction "c31_c31") (pintype "bidirectional"))
    )
    (net (code "211") (name "/TCK") (class "Default")
      (node (ref "J15") (pin "d29") (pinfunction "d29_d29") (pintype "bidirectional"))
    )
    (net (code "212") (name "/TDI") (class "Default")
      (node (ref "J15") (pin "d30") (pinfunction "d30_d30") (pintype "bidirectional"))
    )
    (net (code "213") (name "/TDO") (class "Default")
      (node (ref "J15") (pin "d31") (pinfunction "d31_d31") (pintype "bidirectional"))
    )
    (net (code "214") (name "/TMS") (class "Default")
      (node (ref "J15") (pin "d33") (pinfunction "d33_d33") (pintype "bidirectional"))
    )
    (net (code "215") (name "/TRST_L") (class "Default")
      (node (ref "J15") (pin "d34") (pinfunction "d34_d34") (pintype "bidirectional"))
    )
    (net (code "216") (name "/VADJ") (class "Default")
      (node (ref "C10") (pin "2") (pinfunction "2_2") (pintype "passive"))
      (node (ref "C7") (pin "1") (pinfunction "1_1") (pintype "passive"))
      (node (ref "C8") (pin "1") (pinfunction "1_1") (pintype "passive"))
      (node (ref "C9") (pin "1") (pinfunction "1_1") (pintype "passive"))
      (node (ref "J15") (pin "e39") (pinfunction "e39_e39") (pintype "bidirectional"))
      (node (ref "J15") (pin "f40") (pinfunction "f40_f40") (pintype "bidirectional"))
      (node (ref "J15") (pin "g39") (pinfunction "g39_g39") (pintype "bidirectional"))
      (node (ref "J15") (pin "h40") (pinfunction "h40_h40") (pintype "bidirectional"))
    )
    (net (code "218") (name "/VREF_A_M2C") (class "Default")
      (node (ref "J15") (pin "h1") (pinfunction "h1_h1") (pintype "bidirectional"))
    )
    (net (code "219") (name "/VREF_B_M2C") (class "Default")
      (node (ref "J15") (pin "k1") (pinfunction "k1_k1") (pintype "bidirectional"))
    )
    (net (code "231") (name "GND") (class "Default")
      (node (ref "B1") (pin "1") (pinfunction "1_1") (pintype "bidirectional"))
      (node (ref "B2") (pin "1") (pinfunction "1_1") (pintype "bidirectional"))
      (node (ref "B3") (pin "1") (pinfunction "1_1") (pintype "bidirectional"))
      (node (ref "B4") (pin "1") (pinfunction "1_1") (pintype "bidirectional"))
      (node (ref "C1") (pin "2") (pinfunction "2_2") (pintype "passive"))
      (node (ref "C10") (pin "1") (pinfunction "1_1") (pintype "passive"))
      (node (ref "C11") (pin "1") (pinfunction "1_1") (pintype "passive"))
      (node (ref "C12") (pin "2") (pinfunction "2_2") (pintype "passive"))
      (node (ref "C13") (pin "2") (pinfunction "2_2") (pintype "passive"))
      (node (ref "C14") (pin "2") (pinfunction "2_2") (pintype "passive"))
      (node (ref "C15") (pin "1") (pinfunction "1_1") (pintype "passive"))
      (node (ref "C16") (pin "2") (pinfunction "2_2") (pintype "passive"))
      (node (ref "C17") (pin "2") (pinfunction "2_2") (pintype "passive"))
      (node (ref "C2") (pin "2") (pinfunction "2_2") (pintype "passive"))
      (node (ref "C3") (pin "2") (pinfunction "2_2") (pintype "passive"))
      (node (ref "C4") (pin "1") (pinfunction "1_1") (pintype "passive"))
      (node (ref "C5") (pin "2") (pinfunction "2_2") (pintype "passive"))
      (node (ref "C6") (pin "1") (pinfunction "1_1") (pintype "passive"))
      (node (ref "C7") (pin "2") (pinfunction "2_2") (pintype "passive"))
      (node (ref "C8") (pin "2") (pinfunction "2_2") (pintype "passive"))
      (node (ref "C9") (pin "2") (pinfunction "2_2") (pintype "passive"))
      (node (ref "J15") (pin "a1") (pinfunction "a1_a1") (pintype "bidirectional"))
      (node (ref "J15") (pin "a12") (pinfunction "a12_a12") (pintype "bidirectional"))
      (node (ref "J15") (pin "a13") (pinfunction "a13_a13") (pintype "bidirectional"))
      (node (ref "J15") (pin "a16") (pinfunction "a16_a16") (pintype "bidirectional"))
      (node (ref "J15") (pin "a17") (pinfunction "a17_a17") (pintype "bidirectional"))
      (node (ref "J15") (pin "a20") (pinfunction "a20_a20") (pintype "bidirectional"))
      (node (ref "J15") (pin "a21") (pinfunction "a21_a21") (pintype "bidirectional"))
      (node (ref "J15") (pin "a24") (pinfunction "a24_a24") (pintype "bidirectional"))
      (node (ref "J15") (pin "a25") (pinfunction "a25_a25") (pintype "bidirectional"))
      (node (ref "J15") (pin "a28") (pinfunction "a28_a28") (pintype "bidirectional"))
      (node (ref "J15") (pin "a29") (pinfunction "a29_a29") (pintype "bidirectional"))
      (node (ref "J15") (pin "a32") (pinfunction "a32_a32") (pintype "bidirectional"))
      (node (ref "J15") (pin "a33") (pinfunction "a33_a33") (pintype "bidirectional"))
      (node (ref "J15") (pin "a36") (pinfunction "a36_a36") (pintype "bidirectional"))
      (node (ref "J15") (pin "a37") (pinfunction "a37_a37") (pintype "bidirectional"))
      (node (ref "J15") (pin "a4") (pinfunction "a4_a4") (pintype "bidirectional"))
      (node (ref "J15") (pin "a40") (pinfunction "a40_a40") (pintype "bidirectional"))
      (node (ref "J15") (pin "a5") (pinfunction "a5_a5") (pintype "bidirectional"))
      (node (ref "J15") (pin "a8") (pinfunction "a8_a8") (pintype "bidirectional"))
      (node (ref "J15") (pin "a9") (pinfunction "a9_a9") (pintype "bidirectional"))
      (node (ref "J15") (pin "b10") (pinfunction "b10_b10") (pintype "bidirectional"))
      (node (ref "J15") (pin "b11") (pinfunction "b11_b11") (pintype "bidirectional"))
      (node (ref "J15") (pin "b14") (pinfunction "b14_b14") (pintype "bidirectional"))
      (node (ref "J15") (pin "b15") (pinfunction "b15_b15") (pintype "bidirectional"))
      (node (ref "J15") (pin "b18") (pinfunction "b18_b18") (pintype "bidirectional"))
      (node (ref "J15") (pin "b19") (pinfunction "b19_b19") (pintype "bidirectional"))
      (node (ref "J15") (pin "b2") (pinfunction "b2_b2") (pintype "bidirectional"))
      (node (ref "J15") (pin "b22") (pinfunction "b22_b22") (pintype "bidirectional"))
      (node (ref "J15") (pin "b23") (pinfunction "b23_b23") (pintype "bidirectional"))
      (node (ref "J15") (pin "b26") (pinfunction "b26_b26") (pintype "bidirectional"))
      (node (ref "J15") (pin "b27") (pinfunction "b27_b27") (pintype "bidirectional"))
      (node (ref "J15") (pin "b3") (pinfunction "b3_b3") (pintype "bidirectional"))
      (node (ref "J15") (pin "b30") (pinfunction "b30_b30") (pintype "bidirectional"))
      (node (ref "J15") (pin "b31") (pinfunction "b31_b31") (pintype "bidirectional"))
      (node (ref "J15") (pin "b34") (pinfunction "b34_b34") (pintype "bidirectional"))
      (node (ref "J15") (pin "b35") (pinfunction "b35_b35") (pintype "bidirectional"))
      (node (ref "J15") (pin "b38") (pinfunction "b38_b38") (pintype "bidirectional"))
      (node (ref "J15") (pin "b39") (pinfunction "b39_b39") (pintype "bidirectional"))
      (node (ref "J15") (pin "b6") (pinfunction "b6_b6") (pintype "bidirectional"))
      (node (ref "J15") (pin "b7") (pinfunction "b7_b7") (pintype "bidirectional"))
      (node (ref "J15") (pin "c1") (pinfunction "c1_c1") (pintype "bidirectional"))
      (node (ref "J15") (pin "c12") (pinfunction "c12_c12") (pintype "bidirectional"))
      (node (ref "J15") (pin "c13") (pinfunction "c13_c13") (pintype "bidirectional"))
      (node (ref "J15") (pin "c16") (pinfunction "c16_c16") (pintype "bidirectional"))
      (node (ref "J15") (pin "c17") (pinfunction "c17_c17") (pintype "bidirectional"))
      (node (ref "J15") (pin "c20") (pinfunction "c20_c20") (pintype "bidirectional"))
      (node (ref "J15") (pin "c21") (pinfunction "c21_c21") (pintype "bidirectional"))
      (node (ref "J15") (pin "c24") (pinfunction "c24_c24") (pintype "bidirectional"))
      (node (ref "J15") (pin "c25") (pinfunction "c25_c25") (pintype "bidirectional"))
      (node (ref "J15") (pin "c28") (pinfunction "c28_c28") (pintype "bidirectional"))
      (node (ref "J15") (pin "c29") (pinfunction "c29_c29") (pintype "bidirectional"))
      (node (ref "J15") (pin "c32") (pinfunction "c32_c32") (pintype "bidirectional"))
      (node (ref "J15") (pin "c33") (pinfunction "c33_c33") (pintype "bidirectional"))
      (node (ref "J15") (pin "c36") (pinfunction "c36_c36") (pintype "bidirectional"))
      (node (ref "J15") (pin "c38") (pinfunction "c38_c38") (pintype "bidirectional"))
      (node (ref "J15") (pin "c4") (pinfunction "c4_c4") (pintype "bidirectional"))
      (node (ref "J15") (pin "c40") (pinfunction "c40_c40") (pintype "bidirectional"))
      (node (ref "J15") (pin "c5") (pinfunction "c5_c5") (pintype "bidirectional"))
      (node (ref "J15") (pin "c8") (pinfunction "c8_c8") (pintype "bidirectional"))
      (node (ref "J15") (pin "c9") (pinfunction "c9_c9") (pintype "bidirectional"))
      (node (ref "J15") (pin "d10") (pinfunction "d10_d10") (pintype "bidirectional"))
      (node (ref "J15") (pin "d13") (pinfunction "d13_d13") (pintype "bidirectional"))
      (node (ref "J15") (pin "d16") (pinfunction "d16_d16") (pintype "bidirectional"))
      (node (ref "J15") (pin "d19") (pinfunction "d19_d19") (pintype "bidirectional"))
      (node (ref "J15") (pin "d2") (pinfunction "d2_d2") (pintype "bidirectional"))
      (node (ref "J15") (pin "d22") (pinfunction "d22_d22") (pintype "bidirectional"))
      (node (ref "J15") (pin "d25") (pinfunction "d25_d25") (pintype "bidirectional"))
      (node (ref "J15") (pin "d28") (pinfunction "d28_d28") (pintype "bidirectional"))
      (node (ref "J15") (pin "d3") (pinfunction "d3_d3") (pintype "bidirectional"))
      (node (ref "J15") (pin "d37") (pinfunction "d37_d37") (pintype "bidirectional"))
      (node (ref "J15") (pin "d39") (pinfunction "d39_d39") (pintype "bidirectional"))
      (node (ref "J15") (pin "d6") (pinfunction "d6_d6") (pintype "bidirectional"))
      (node (ref "J15") (pin "d7") (pinfunction "d7_d7") (pintype "bidirectional"))
      (node (ref "J15") (pin "e1") (pinfunction "e1_e1") (pintype "bidirectional"))
      (node (ref "J15") (pin "e11") (pinfunction "e11_e11") (pintype "bidirectional"))
      (node (ref "J15") (pin "e14") (pinfunction "e14_e14") (pintype "bidirectional"))
      (node (ref "J15") (pin "e17") (pinfunction "e17_e17") (pintype "bidirectional"))
      (node (ref "J15") (pin "e20") (pinfunction "e20_e20") (pintype "bidirectional"))
      (node (ref "J15") (pin "e23") (pinfunction "e23_e23") (pintype "bidirectional"))
      (node (ref "J15") (pin "e26") (pinfunction "e26_e26") (pintype "bidirectional"))
      (node (ref "J15") (pin "e29") (pinfunction "e29_e29") (pintype "bidirectional"))
      (node (ref "J15") (pin "e32") (pinfunction "e32_e32") (pintype "bidirectional"))
      (node (ref "J15") (pin "e35") (pinfunction "e35_e35") (pintype "bidirectional"))
      (node (ref "J15") (pin "e38") (pinfunction "e38_e38") (pintype "bidirectional"))
      (node (ref "J15") (pin "e4") (pinfunction "e4_e4") (pintype "bidirectional"))
      (node (ref "J15") (pin "e40") (pinfunction "e40_e40") (pintype "bidirectional"))
      (node (ref "J15") (pin "e5") (pinfunction "e5_e5") (pintype "bidirectional"))
      (node (ref "J15") (pin "e8") (pinfunction "e8_e8") (pintype "bidirectional"))
      (node (ref "J15") (pin "f12") (pinfunction "f12_f12") (pintype "bidirectional"))
      (node (ref "J15") (pin "f15") (pinfunction "f15_f15") (pintype "bidirectional"))
      (node (ref "J15") (pin "f18") (pinfunction "f18_f18") (pintype "bidirectional"))
      (node (ref "J15") (pin "f2") (pinfunction "f2_f2") (pintype "bidirectional"))
      (node (ref "J15") (pin "f21") (pinfunction "f21_f21") (pintype "bidirectional"))
      (node (ref "J15") (pin "f24") (pinfunction "f24_f24") (pintype "bidirectional"))
      (node (ref "J15") (pin "f27") (pinfunction "f27_f27") (pintype "bidirectional"))
      (node (ref "J15") (pin "f3") (pinfunction "f3_f3") (pintype "bidirectional"))
      (node (ref "J15") (pin "f30") (pinfunction "f30_f30") (pintype "bidirectional"))
      (node (ref "J15") (pin "f33") (pinfunction "f33_f33") (pintype "bidirectional"))
      (node (ref "J15") (pin "f36") (pinfunction "f36_f36") (pintype "bidirectional"))
      (node (ref "J15") (pin "f39") (pinfunction "f39_f39") (pintype "bidirectional"))
      (node (ref "J15") (pin "f6") (pinfunction "f6_f6") (pintype "bidirectional"))
      (node (ref "J15") (pin "f9") (pinfunction "f9_f9") (pintype "bidirectional"))
      (node (ref "J15") (pin "g1") (pinfunction "g1_g1") (pintype "bidirectional"))
      (node (ref "J15") (pin "g11") (pinfunction "g11_g11") (pintype "bidirectional"))
      (node (ref "J15") (pin "g14") (pinfunction "g14_g14") (pintype "bidirectional"))
      (node (ref "J15") (pin "g17") (pinfunction "g17_g17") (pintype "bidirectional"))
      (node (ref "J15") (pin "g20") (pinfunction "g20_g20") (pintype "bidirectional"))
      (node (ref "J15") (pin "g23") (pinfunction "g23_g23") (pintype "bidirectional"))
      (node (ref "J15") (pin "g26") (pinfunction "g26_g26") (pintype "bidirectional"))
      (node (ref "J15") (pin "g29") (pinfunction "g29_g29") (pintype "bidirectional"))
      (node (ref "J15") (pin "g32") (pinfunction "g32_g32") (pintype "bidirectional"))
      (node (ref "J15") (pin "g35") (pinfunction "g35_g35") (pintype "bidirectional"))
      (node (ref "J15") (pin "g38") (pinfunction "g38_g38") (pintype "bidirectional"))
      (node (ref "J15") (pin "g4") (pinfunction "g4_g4") (pintype "bidirectional"))
      (node (ref "J15") (pin "g40") (pinfunction "g40_g40") (pintype "bidirectional"))
      (node (ref "J15") (pin "g5") (pinfunction "g5_g5") (pintype "bidirectional"))
      (node (ref "J15") (pin "g8") (pinfunction "g8_g8") (pintype "bidirectional"))
      (node (ref "J15") (pin "h12") (pinfunction "h12_h12") (pintype "bidirectional"))
      (node (ref "J15") (pin "h15") (pinfunction "h15_h15") (pintype "bidirectional"))
      (node (ref "J15") (pin "h18") (pinfunction "h18_h18") (pintype "bidirectional"))
      (node (ref "J15") (pin "h21") (pinfunction "h21_h21") (pintype "bidirectional"))
      (node (ref "J15") (pin "h24") (pinfunction "h24_h24") (pintype "bidirectional"))
      (node (ref "J15") (pin "h27") (pinfunction "h27_h27") (pintype "bidirectional"))
      (node (ref "J15") (pin "h3") (pinfunction "h3_h3") (pintype "bidirectional"))
      (node (ref "J15") (pin "h30") (pinfunction "h30_h30") (pintype "bidirectional"))
      (node (ref "J15") (pin "h33") (pinfunction "h33_h33") (pintype "bidirectional"))
      (node (ref "J15") (pin "h36") (pinfunction "h36_h36") (pintype "bidirectional"))
      (node (ref "J15") (pin "h39") (pinfunction "h39_h39") (pintype "bidirectional"))
      (node (ref "J15") (pin "h6") (pinfunction "h6_h6") (pintype "bidirectional"))
      (node (ref "J15") (pin "h9") (pinfunction "h9_h9") (pintype "bidirectional"))
      (node (ref "J15") (pin "j1") (pinfunction "j1_j1") (pintype "bidirectional"))
      (node (ref "J15") (pin "j11") (pinfunction "j11_j11") (pintype "bidirectional"))
      (node (ref "J15") (pin "j14") (pinfunction "j14_j14") (pintype "bidirectional"))
      (node (ref "J15") (pin "j17") (pinfunction "j17_j17") (pintype "bidirectional"))
      (node (ref "J15") (pin "j20") (pinfunction "j20_j20") (pintype "bidirectional"))
      (node (ref "J15") (pin "j23") (pinfunction "j23_j23") (pintype "bidirectional"))
      (node (ref "J15") (pin "j26") (pinfunction "j26_j26") (pintype "bidirectional"))
      (node (ref "J15") (pin "j29") (pinfunction "j29_j29") (pintype "bidirectional"))
      (node (ref "J15") (pin "j32") (pinfunction "j32_j32") (pintype "bidirectional"))
      (node (ref "J15") (pin "j35") (pinfunction "j35_j35") (pintype "bidirectional"))
      (node (ref "J15") (pin "j38") (pinfunction "j38_j38") (pintype "bidirectional"))
      (node (ref "J15") (pin "j4") (pinfunction "j4_j4") (pintype "bidirectional"))
      (node (ref "J15") (pin "j40") (pinfunction "j40_j40") (pintype "bidirectional"))
      (node (ref "J15") (pin "j5") (pinfunction "j5_j5") (pintype "bidirectional"))
      (node (ref "J15") (pin "j8") (pinfunction "j8_j8") (pintype "bidirectional"))
      (node (ref "J15") (pin "k12") (pinfunction "k12_k12") (pintype "bidirectional"))
      (node (ref "J15") (pin "k15") (pinfunction "k15_k15") (pintype "bidirectional"))
      (node (ref "J15") (pin "k18") (pinfunction "k18_k18") (pintype "bidirectional"))
      (node (ref "J15") (pin "k2") (pinfunction "k2_k2") (pintype "bidirectional"))
      (node (ref "J15") (pin "k21") (pinfunction "k21_k21") (pintype "bidirectional"))
      (node (ref "J15") (pin "k24") (pinfunction "k24_k24") (pintype "bidirectional"))
      (node (ref "J15") (pin "k27") (pinfunction "k27_k27") (pintype "bidirectional"))
      (node (ref "J15") (pin "k3") (pinfunction "k3_k3") (pintype "bidirectional"))
      (node (ref "J15") (pin "k30") (pinfunction "k30_k30") (pintype "bidirectional"))
      (node (ref "J15") (pin "k33") (pinfunction "k33_k33") (pintype "bidirectional"))
      (node (ref "J15") (pin "k36") (pinfunction "k36_k36") (pintype "bidirectional"))
      (node (ref "J15") (pin "k39") (pinfunction "k39_k39") (pintype "bidirectional"))
      (node (ref "J15") (pin "k6") (pinfunction "k6_k6") (pintype "bidirectional"))
      (node (ref "J15") (pin "k9") (pinfunction "k9_k9") (pintype "bidirectional"))
    )
    (net (code "232") (name "unconnected-(J15-Pada14)") (class "Default")
      (node (ref "J15") (pin "a14") (pinfunction "a14_a14") (pintype "bidirectional"))
    )
    (net (code "233") (name "unconnected-(J15-Pada15)") (class "Default")
      (node (ref "J15") (pin "a15") (pinfunction "a15_a15") (pintype "bidirectional"))
    )
    (net (code "234") (name "unconnected-(J15-Pada18)") (class "Default")
      (node (ref "J15") (pin "a18") (pinfunction "a18_a18") (pintype "bidirectional"))
    )
    (net (code "235") (name "unconnected-(J15-Pada19)") (class "Default")
      (node (ref "J15") (pin "a19") (pinfunction "a19_a19") (pintype "bidirectional"))
    )
    (net (code "236") (name "unconnected-(J15-Pada34)") (class "Default")
      (node (ref "J15") (pin "a34") (pinfunction "a34_a34") (pintype "bidirectional"))
    )
    (net (code "237") (name "unconnected-(J15-Pada35)") (class "Default")
      (node (ref "J15") (pin "a35") (pinfunction "a35_a35") (pintype "bidirectional"))
    )
    (net (code "238") (name "unconnected-(J15-Pada38)") (class "Default")
      (node (ref "J15") (pin "a38") (pinfunction "a38_a38") (pintype "bidirectional"))
    )
    (net (code "239") (name "unconnected-(J15-Pada39)") (class "Default")
      (node (ref "J15") (pin "a39") (pinfunction "a39_a39") (pintype "bidirectional"))
    )
    (net (code "240") (name "unconnected-(J15-Padb4)") (class "Default")
      (node (ref "J15") (pin "b4") (pinfunction "b4_b4") (pintype "bidirectional"))
    )
    (net (code "241") (name "unconnected-(J15-Padb5)") (class "Default")
      (node (ref "J15") (pin "b5") (pinfunction "b5_b5") (pintype "bidirectional"))
    )
    (net (code "242") (name "unconnected-(J15-Padb8)") (class "Default")
      (node (ref "J15") (pin "b8") (pinfunction "b8_b8") (pintype "bidirectional"))
    )
    (net (code "243") (name "unconnected-(J15-Padb9)") (class "Default")
      (node (ref "J15") (pin "b9") (pinfunction "b9_b9") (pintype "bidirectional"))
    )
    (net (code "244") (name "unconnected-(J15-Padb12)") (class "Default")
      (node (ref "J15") (pin "b12") (pinfunction "b12_b12") (pintype "bidirectional"))
    )
    (net (code "245") (name "unconnected-(J15-Padb13)") (class "Default")
      (node (ref "J15") (pin "b13") (pinfunction "b13_b13") (pintype "bidirectional"))
    )
    (net (code "246") (name "unconnected-(J15-Padb16)") (class "Default")
      (node (ref "J15") (pin "b16") (pinfunction "b16_b16") (pintype "bidirectional"))
    )
    (net (code "247") (name "unconnected-(J15-Padb17)") (class "Default")
      (node (ref "J15") (pin "b17") (pinfunction "b17_b17") (pintype "bidirectional"))
    )
    (net (code "248") (name "unconnected-(J15-Padb24)") (class "Default")
      (node (ref "J15") (pin "b24") (pinfunction "b24_b24") (pintype "bidirectional"))
    )
    (net (code "249") (name "unconnected-(J15-Padb25)") (class "Default")
      (node (ref "J15") (pin "b25") (pinfunction "b25_b25") (pintype "bidirectional"))
    )
    (net (code "250") (name "unconnected-(J15-Padb28)") (class "Default")
      (node (ref "J15") (pin "b28") (pinfunction "b28_b28") (pintype "bidirectional"))
    )
    (net (code "251") (name "unconnected-(J15-Padb29)") (class "Default")
      (node (ref "J15") (pin "b29") (pinfunction "b29_b29") (pintype "bidirectional"))
    )
    (net (code "252") (name "unconnected-(J15-Padb32)") (class "Default")
      (node (ref "J15") (pin "b32") (pinfunction "b32_b32") (pintype "bidirectional"))
    )
    (net (code "253") (name "unconnected-(J15-Padb33)") (class "Default")
      (node (ref "J15") (pin "b33") (pinfunction "b33_b33") (pintype "bidirectional"))
    )
    (net (code "254") (name "unconnected-(J15-Padb36)") (class "Default")
      (node (ref "J15") (pin "b36") (pinfunction "b36_b36") (pintype "bidirectional"))
    )
    (net (code "255") (name "unconnected-(J15-Padb37)") (class "Default")
      (node (ref "J15") (pin "b37") (pinfunction "b37_b37") (pintype "bidirectional"))
    )
    (net (code "256") (name "unconnected-(J15-Padb40)") (class "Default")
      (node (ref "J15") (pin "b40") (pinfunction "b40_b40") (pintype "bidirectional"))
    )
    (net (code "257") (name "unconnected-(J15-Padj39)") (class "Default")
      (node (ref "J15") (pin "j39") (pinfunction "j39_j39") (pintype "bidirectional"))
    )
    (net (code "258") (name "unconnected-(J15-Padk40)") (class "Default")
      (node (ref "J15") (pin "k40") (pinfunction "k40_k40") (pintype "bidirectional"))
    )
  )
)
